# Power.net
KiCad netlist of a schematic drawn in Altium Designer
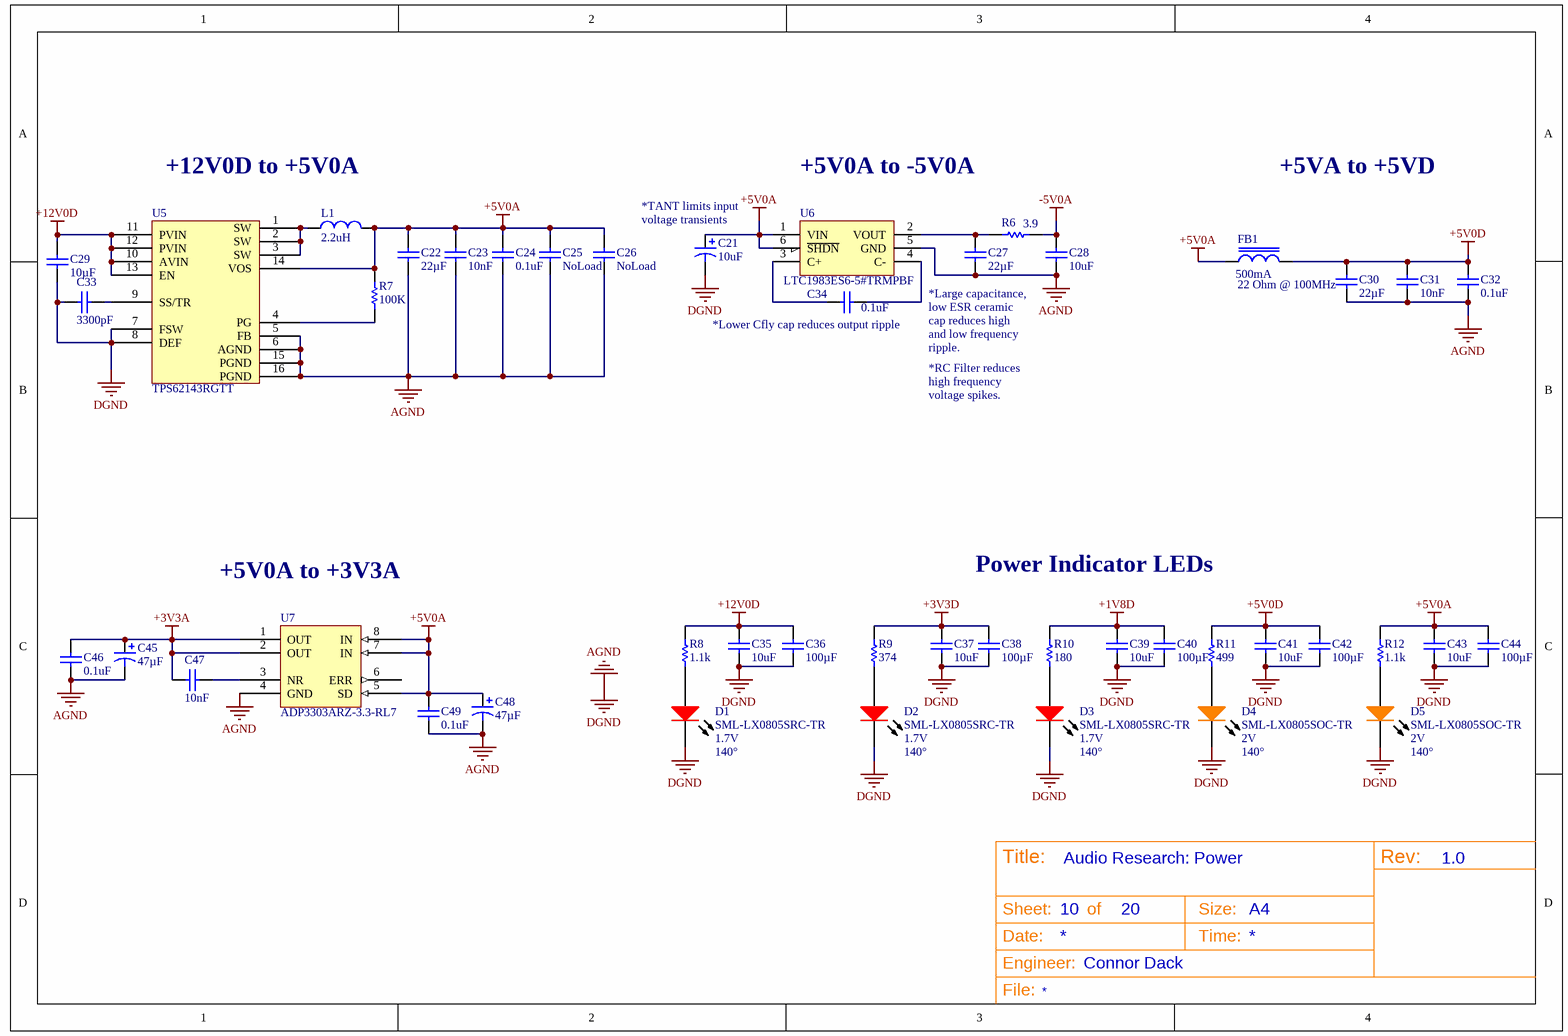
[diagram p0: Power.SchDoc]

(export (version "E")
  (design (tool "Eeschema 10.0.6"))
  (components
    (comp (ref "C21")
      (value "TR3A106K010C0900")
      (footprint "C1206_TANT")
      (description "CAP TANT 10UF 10V 10% 1206")
      (fields
        (field (name "MANUFACTURER") "Vishay Sprague")
        (field (name "TOLERANCE") "10%")
        (field (name "CAPACITANCE") "10uF")
      )
      (libsource (lib "Schematic_Components_CD") (part "TR3A106K010C0900"))
    )
    (comp (ref "C22")
      (value "CL21A226KPCLRNC")
      (footprint "6-0805_L")
      (description "CAP CER 22UF 10V X5R 0805")
      (fields
        (field (name "MANUFACTURER") "Samsung Electro-Mechanics America, Inc.")
        (field (name "TOLERANCE") "±10%")
        (field (name "CAPACITANCE") "22µF")
      )
      (libsource (lib "Schematic_Components") (part "CL21A226KPCLRNC"))
    )
    (comp (ref "C23")
      (value "C1608X8R2A103K080AA")
      (footprint "3-0603_L")
      (description "CAP CER 10000PF 100V X8R 0603")
      (fields
        (field (name "MANUFACTURER") "TDK")
        (field (name "TOLERANCE") "10%")
        (field (name "CAPACITANCE") "10nF")
      )
      (libsource (lib "Schematic_Components_CD") (part "C1608X8R2A103K080AA"))
    )
    (comp (ref "C24")
      (value "CL10F104ZO8NNNC")
      (footprint "3-0603_L")
      (description "CAP CER 0.1UF 16V Y5V 0603")
      (fields
        (field (name "MANUFACTURER") "Samsung")
        (field (name "TOLERANCE") "80%")
        (field (name "CAPACITANCE") "0.1uF")
      )
      (libsource (lib "Schematic_Components_CD") (part "CL10F104ZO8NNNC"))
    )
    (comp (ref "C25")
      (value "CAP 0603")
      (footprint "3-0603_L")
      (description "CAP 0603 SMD - NoLoad")
      (fields (field (name "CAPACITANCE") "NoLoad"))
      (libsource (lib "Schematic_Components_CD") (part "CAP 0603"))
    )
    (comp (ref "C26")
      (value "CAP 0603")
      (footprint "3-0603_L")
      (description "CAP 0603 SMD - NoLoad")
      (fields (field (name "CAPACITANCE") "NoLoad"))
      (libsource (lib "Schematic_Components_CD") (part "CAP 0603"))
    )
    (comp (ref "C27")
      (value "C3216X6S1C226M")
      (footprint "C1206")
      (description "CAP CER 22UF 16V 20% X6S 1206")
      (fields
        (field (name "MANUFACTURER") "TDK Corporation")
        (field (name "TOLERANCE") "±20%")
        (field (name "CAPACITANCE") "22µF")
      )
      (libsource (lib "Schematic_Components") (part "C3216X6S1C226M"))
    )
    (comp (ref "C28")
      (value "GRM188R61A106ME69D")
      (footprint "3-0603_L")
      (description "CAP CER 10UF 10V X5R 0603")
      (fields
        (field (name "MANUFACTURER") "Murata")
        (field (name "TOLERANCE") "20%")
        (field (name "CAPACITANCE") "10uF")
      )
      (libsource (lib "Schematic_Components_CD") (part "GRM188R61A106ME69D"))
    )
    (comp (ref "C29")
      (value "C3216X5R1H106K")
      (footprint "C1206")
      (description "CAP CER 10UF 50V 10% X5R 1206")
      (fields
        (field (name "MANUFACTURER") "TDK Corporation")
        (field (name "TOLERANCE") "±10%")
        (field (name "CAPACITANCE") "10µF")
      )
      (libsource (lib "Schematic_Components") (part "C3216X5R1H106K"))
    )
    (comp (ref "C30")
      (value "CL21A226KPCLRNC")
      (footprint "6-0805_L")
      (description "CAP CER 22UF 10V X5R 0805")
      (fields
        (field (name "MANUFACTURER") "Samsung Electro-Mechanics America, Inc.")
        (field (name "TOLERANCE") "±10%")
        (field (name "CAPACITANCE") "22µF")
      )
      (libsource (lib "Schematic_Components") (part "CL21A226KPCLRNC"))
    )
    (comp (ref "C31")
      (value "C1608X8R2A103K080AA")
      (footprint "3-0603_L")
      (description "CAP CER 10000PF 100V X8R 0603")
      (fields
        (field (name "MANUFACTURER") "TDK")
        (field (name "TOLERANCE") "10%")
        (field (name "CAPACITANCE") "10nF")
      )
      (libsource (lib "Schematic_Components_CD") (part "C1608X8R2A103K080AA"))
    )
    (comp (ref "C32")
      (value "CL10F104ZO8NNNC")
      (footprint "3-0603_L")
      (description "CAP CER 0.1UF 16V Y5V 0603")
      (fields
        (field (name "MANUFACTURER") "Samsung")
        (field (name "TOLERANCE") "80%")
        (field (name "CAPACITANCE") "0.1uF")
      )
      (libsource (lib "Schematic_Components_CD") (part "CL10F104ZO8NNNC"))
    )
    (comp (ref "C33")
      (value "GRM2165C1H332JA01D")
      (footprint "6-0805_L")
      (description "CAP CER 3300PF 50V NP0 0805")
      (fields
        (field (name "MANUFACTURER") "Murata Electronics North America")
        (field (name "TOLERANCE") "±5%")
        (field (name "CAPACITANCE") "3300pF")
      )
      (libsource (lib "Schematic_Components") (part "GRM2165C1H332JA01D"))
    )
    (comp (ref "C34")
      (value "CL10F104ZO8NNNC")
      (footprint "3-0603_L")
      (description "CAP CER 0.1UF 16V Y5V 0603")
      (fields
        (field (name "MANUFACTURER") "Samsung")
        (field (name "TOLERANCE") "80%")
        (field (name "CAPACITANCE") "0.1uF")
      )
      (libsource (lib "Schematic_Components_CD") (part "CL10F104ZO8NNNC"))
    )
    (comp (ref "C35")
      (value "GRM188R61A106ME69D")
      (footprint "3-0603_L")
      (description "CAP CER 10UF 10V X5R 0603")
      (fields
        (field (name "MANUFACTURER") "Murata")
        (field (name "TOLERANCE") "20%")
        (field (name "CAPACITANCE") "10uF")
      )
      (libsource (lib "Schematic_Components_CD") (part "GRM188R61A106ME69D"))
    )
    (comp (ref "C36")
      (value "CL32X107MQVNNNE")
      (footprint "C1210X25_L")
      (description "100µF 6.3V Ceramic Capacitor X6S 1210 (3225 Metric) 0.126\" L x 0.098\" W (3.20mm x 2.50mm)")
      (fields
        (field (name "MANUFACTURER") "Samsung Electro-Mechanics America, Inc.")
        (field (name "TOLERANCE") "±20%")
        (field (name "CAPACITANCE") "100µF")
      )
      (libsource (lib "Schematic_Components") (part "CL32X107MQVNNNE"))
    )
    (comp (ref "C37")
      (value "GRM188R61A106ME69D")
      (footprint "3-0603_L")
      (description "CAP CER 10UF 10V X5R 0603")
      (fields
        (field (name "MANUFACTURER") "Murata")
        (field (name "TOLERANCE") "20%")
        (field (name "CAPACITANCE") "10uF")
      )
      (libsource (lib "Schematic_Components_CD") (part "GRM188R61A106ME69D"))
    )
    (comp (ref "C38")
      (value "CL32X107MQVNNNE")
      (footprint "C1210X25_L")
      (description "100µF 6.3V Ceramic Capacitor X6S 1210 (3225 Metric) 0.126\" L x 0.098\" W (3.20mm x 2.50mm)")
      (fields
        (field (name "MANUFACTURER") "Samsung Electro-Mechanics America, Inc.")
        (field (name "TOLERANCE") "±20%")
        (field (name "CAPACITANCE") "100µF")
      )
      (libsource (lib "Schematic_Components") (part "CL32X107MQVNNNE"))
    )
    (comp (ref "C39")
      (value "GRM188R61A106ME69D")
      (footprint "3-0603_L")
      (description "CAP CER 10UF 10V X5R 0603")
      (fields
        (field (name "MANUFACTURER") "Murata")
        (field (name "TOLERANCE") "20%")
        (field (name "CAPACITANCE") "10uF")
      )
      (libsource (lib "Schematic_Components_CD") (part "GRM188R61A106ME69D"))
    )
    (comp (ref "C40")
      (value "CL32X107MQVNNNE")
      (footprint "C1210X25_L")
      (description "100µF 6.3V Ceramic Capacitor X6S 1210 (3225 Metric) 0.126\" L x 0.098\" W (3.20mm x 2.50mm)")
      (fields
        (field (name "MANUFACTURER") "Samsung Electro-Mechanics America, Inc.")
        (field (name "TOLERANCE") "±20%")
        (field (name "CAPACITANCE") "100µF")
      )
      (libsource (lib "Schematic_Components") (part "CL32X107MQVNNNE"))
    )
    (comp (ref "C41")
      (value "GRM188R61A106ME69D")
      (footprint "3-0603_L")
      (description "CAP CER 10UF 10V X5R 0603")
      (fields
        (field (name "MANUFACTURER") "Murata")
        (field (name "TOLERANCE") "20%")
        (field (name "CAPACITANCE") "10uF")
      )
      (libsource (lib "Schematic_Components_CD") (part "GRM188R61A106ME69D"))
    )
    (comp (ref "C42")
      (value "CL32X107MQVNNNE")
      (footprint "C1210X25_L")
      (description "100µF 6.3V Ceramic Capacitor X6S 1210 (3225 Metric) 0.126\" L x 0.098\" W (3.20mm x 2.50mm)")
      (fields
        (field (name "MANUFACTURER") "Samsung Electro-Mechanics America, Inc.")
        (field (name "TOLERANCE") "±20%")
        (field (name "CAPACITANCE") "100µF")
      )
      (libsource (lib "Schematic_Components") (part "CL32X107MQVNNNE"))
    )
    (comp (ref "C43")
      (value "GRM188R61A106ME69D")
      (footprint "3-0603_L")
      (description "CAP CER 10UF 10V X5R 0603")
      (fields
        (field (name "MANUFACTURER") "Murata")
        (field (name "TOLERANCE") "20%")
        (field (name "CAPACITANCE") "10uF")
      )
      (libsource (lib "Schematic_Components_CD") (part "GRM188R61A106ME69D"))
    )
    (comp (ref "C44")
      (value "CL32X107MQVNNNE")
      (footprint "C1210X25_L")
      (description "100µF 6.3V Ceramic Capacitor X6S 1210 (3225 Metric) 0.126\" L x 0.098\" W (3.20mm x 2.50mm)")
      (fields
        (field (name "MANUFACTURER") "Samsung Electro-Mechanics America, Inc.")
        (field (name "TOLERANCE") "±20%")
        (field (name "CAPACITANCE") "100µF")
      )
      (libsource (lib "Schematic_Components") (part "CL32X107MQVNNNE"))
    )
    (comp (ref "C45")
      (value "EEE-FT1H470AP")
      (footprint "ALUMCAPC630D_D")
      (description "CAP ALUM 47UF 50V 20% SMD")
      (fields
        (field (name "MANUFACTURER") "Panasonic - ECG")
        (field (name "TOLERANCE") "±20%")
        (field (name "CAPACITANCE") "47µF")
      )
      (libsource (lib "Schematic_Components") (part "EEE-FT1H470AP"))
    )
    (comp (ref "C46")
      (value "CL10F104ZO8NNNC")
      (footprint "3-0603_L")
      (description "CAP CER 0.1UF 16V Y5V 0603")
      (fields
        (field (name "MANUFACTURER") "Samsung")
        (field (name "TOLERANCE") "80%")
        (field (name "CAPACITANCE") "0.1uF")
      )
      (libsource (lib "Schematic_Components_CD") (part "CL10F104ZO8NNNC"))
    )
    (comp (ref "C47")
      (value "C1608X8R2A103K080AA")
      (footprint "3-0603_L")
      (description "CAP CER 10000PF 100V X8R 0603")
      (fields
        (field (name "MANUFACTURER") "TDK")
        (field (name "TOLERANCE") "10%")
        (field (name "CAPACITANCE") "10nF")
      )
      (libsource (lib "Schematic_Components_CD") (part "C1608X8R2A103K080AA"))
    )
    (comp (ref "C48")
      (value "EEE-FT1H470AP")
      (footprint "ALUMCAPC630D_D")
      (description "CAP ALUM 47UF 50V 20% SMD")
      (fields
        (field (name "MANUFACTURER") "Panasonic - ECG")
        (field (name "TOLERANCE") "±20%")
        (field (name "CAPACITANCE") "47µF")
      )
      (libsource (lib "Schematic_Components") (part "EEE-FT1H470AP"))
    )
    (comp (ref "C49")
      (value "CL10F104ZO8NNNC")
      (footprint "3-0603_L")
      (description "CAP CER 0.1UF 16V Y5V 0603")
      (fields
        (field (name "MANUFACTURER") "Samsung")
        (field (name "TOLERANCE") "80%")
        (field (name "CAPACITANCE") "0.1uF")
      )
      (libsource (lib "Schematic_Components_CD") (part "CL10F104ZO8NNNC"))
    )
    (comp (ref "D1")
      (value "LED_RED 4")
      (footprint "DIOM2012X12L_RED")
      (description "LED 660NM SUPER RED CLR 0805 T/R")
      (fields
        (field (name "MANUFACTURER") "Lumex Opto/Components Inc")
        (field (name "MANUFACTURER PART NUMBER") "SML-LX0805SRC-TR")
        (field (name "VOLTAGE - FORWARD (VF) (TYP)") "1.7V")
        (field (name "VIEWING ANGLE") "140°")
      )
      (libsource (lib "Schematic_Components") (part "LED_RED 4"))
    )
    (comp (ref "D2")
      (value "LED_RED 4")
      (footprint "DIOM2012X12L_RED")
      (description "LED 660NM SUPER RED CLR 0805 T/R")
      (fields
        (field (name "MANUFACTURER") "Lumex Opto/Components Inc")
        (field (name "MANUFACTURER PART NUMBER") "SML-LX0805SRC-TR")
        (field (name "VOLTAGE - FORWARD (VF) (TYP)") "1.7V")
        (field (name "VIEWING ANGLE") "140°")
      )
      (libsource (lib "Schematic_Components") (part "LED_RED 4"))
    )
    (comp (ref "D3")
      (value "LED_RED 4")
      (footprint "DIOM2012X12L_RED")
      (description "LED 660NM SUPER RED CLR 0805 T/R")
      (fields
        (field (name "MANUFACTURER") "Lumex Opto/Components Inc")
        (field (name "MANUFACTURER PART NUMBER") "SML-LX0805SRC-TR")
        (field (name "VOLTAGE - FORWARD (VF) (TYP)") "1.7V")
        (field (name "VIEWING ANGLE") "140°")
      )
      (libsource (lib "Schematic_Components") (part "LED_RED 4"))
    )
    (comp (ref "D4")
      (value "LED_ORANGE 3")
      (footprint "DIOM2012X12L_ORANGE")
      (description "LED 610NM SUPER ORANGE 0805 SMD")
      (fields
        (field (name "MANUFACTURER") "Lumex Opto/Components Inc")
        (field (name "MANUFACTURER PART NUMBER") "SML-LX0805SOC-TR")
        (field (name "VOLTAGE - FORWARD (VF) (TYP)") "2V")
        (field (name "VIEWING ANGLE") "140°")
      )
      (libsource (lib "Schematic_Components") (part "LED_ORANGE 3"))
    )
    (comp (ref "D5")
      (value "LED_ORANGE 3")
      (footprint "DIOM2012X12L_ORANGE")
      (description "LED 610NM SUPER ORANGE 0805 SMD")
      (fields
        (field (name "MANUFACTURER") "Lumex Opto/Components Inc")
        (field (name "MANUFACTURER PART NUMBER") "SML-LX0805SOC-TR")
        (field (name "VOLTAGE - FORWARD (VF) (TYP)") "2V")
        (field (name "VIEWING ANGLE") "140°")
      )
      (libsource (lib "Schematic_Components") (part "LED_ORANGE 3"))
    )
    (comp (ref "FB1")
      (value "BLM18BA220SN1D")
      (footprint "3-0603_L")
      (description "FERRITE CHIP 22 OHM 500MA 0603")
      (fields
        (field (name "MANUFACTURER") "Murata Electronics North America")
        (field (name "CURRENT RATING") "500mA")
        (field (name "IMPEDANCE @ FREQUENCY") "22 Ohm @ 100MHz")
      )
      (libsource (lib "Schematic_Components") (part "BLM18BA220SN1D"))
    )
    (comp (ref "L1")
      (value "2.2uH Ind")
      (footprint "XFL4020")
      (description "Fixed Inductors XFL4020 AEC-Q200 2.2 uH 20 % 8 A")
      (fields
        (field (name "MANUFACTURER") "Coilcraft")
        (field (name "TOLERANCE") "20%")
        (field (name "INDUCTANCE") "2.2uH")
      )
      (libsource (lib "Schematic_Components_CD") (part "XFL4020-222MEB"))
    )
    (comp (ref "R6")
      (value "ERJ-3RQF3R9V")
      (footprint "3-0603_R_L")
      (description "RES 3.9 OHM 1/10W 1% 0603 SMD")
      (fields
        (field (name "MANUFACTURER") "Panasonic Electronic Components")
        (field (name "TOLERANCE") "±1%")
        (field (name "RESISTANCE (OHMS)") "3.9")
      )
      (libsource (lib "Schematic_Components") (part "ERJ-3RQF3R9V"))
    )
    (comp (ref "R7")
      (value "ERJ-3EKF1003V")
      (footprint "3-0603_R_L")
      (description "RES 100K OHM 1/10W 1% 0603 SMD")
      (fields
        (field (name "MANUFACTURER") "Panasonic - ECG")
        (field (name "TOLERANCE") "±1%")
        (field (name "RESISTANCE (OHMS)") "100K")
      )
      (libsource (lib "Schematic_Components") (part "ERJ-3EKF1003V"))
    )
    (comp (ref "R8")
      (value "RMCF0603FT1K10")
      (footprint "3-0603_R_L")
      (description "RES 1.1K OHM 1% 1/10W 0603")
      (fields
        (field (name "MANUFACTURER") "Stackpole Electronics")
        (field (name "TOLERANCE") "1%")
        (field (name "RESISTANCE") "1.1k")
      )
      (libsource (lib "Schematic_Components_CD") (part "RMCF0603FT1K10"))
    )
    (comp (ref "R9")
      (value "ERJ-3EKF3740V")
      (footprint "3-0603_R_L")
      (description "RES SMD 374 OHM 1% 1/10W 0603")
      (fields
        (field (name "MANUFACTURER") "Panasonic Electronic Components")
        (field (name "TOLERANCE") "±1%")
        (field (name "RESISTANCE (OHMS)") "374")
      )
      (libsource (lib "Schematic_Components") (part "ERJ-3EKF3740V"))
    )
    (comp (ref "R10")
      (value "ERA-3AEB181V")
      (footprint "3-0603_R_L")
      (description "RES SMD 180 OHM 0.1% 1/10W 0603")
      (fields
        (field (name "MANUFACTURER") "Panasonic")
        (field (name "MANUFACTURER PART NUMBER") "ERA3AEB181V")
        (field (name "RESISTANCE") "180")
      )
      (libsource (lib "Schematic_Components_CD") (part "ERA-3AEB181V"))
    )
    (comp (ref "R11")
      (value "ERJ-3EKF4990V")
      (footprint "3-0603_R_L")
      (description "RES 499 OHM 1/10W 1% 0603 SMD")
      (fields
        (field (name "MANUFACTURER") "Panasonic - ECG")
        (field (name "TOLERANCE") "±1%")
        (field (name "RESISTANCE (OHMS)") "499")
      )
      (libsource (lib "Schematic_Components") (part "ERJ-3EKF4990V"))
    )
    (comp (ref "R12")
      (value "RMCF0603FT1K10")
      (footprint "3-0603_R_L")
      (description "RES 1.1K OHM 1% 1/10W 0603")
      (fields
        (field (name "MANUFACTURER") "Stackpole Electronics")
        (field (name "TOLERANCE") "1%")
        (field (name "RESISTANCE") "1.1k")
      )
      (libsource (lib "Schematic_Components_CD") (part "RMCF0603FT1K10"))
    )
    (comp (ref "U5")
      (value "IC REG BUCK 5V 2A SYNC 16QFN")
      (footprint "QFN50P300X300X100_HS-17N")
      (description "Buck Switching Regulator IC Positive Fixed 5V 1 Output 2A 16-VFQFN Exposed Pad")
      (fields
        (field (name "MANUFACTURER") "Texas Instruments")
        (field (name "MANUFACTURER PART NUMBER") "TPS62143RGTT")
      )
      (libsource (lib "Schematic_Components_CD") (part "TPS62143RGTT"))
    )
    (comp (ref "U6")
      (value "~")
      (footprint "SOT23-6_L")
      (description "IC REG SWITCHD CAP INV -5V SOT23")
      (fields
        (field (name "MANUFACTURER") "Linear Technology")
        (field (name "MANUFACTURER PART NUMBER") "LTC1983ES6-5#TRMPBF")
      )
      (libsource (lib "Schematic_Components") (part "LTC1983ES6-5#TRMPBF"))
    )
    (comp (ref "U7")
      (value "ADP3303ARZ-3.3-RL7")
      (footprint "SOIC127P600X175-8L")
      (description "Linear Voltage Regulator IC Positive Fixed 1 Output 3.3V 200mA 8-SOIC")
      (fields
        (field (name "MANUFACTURER") "Analog Devices Inc.")
        (field (name "MANUFACTURER PART NUMBER") "ADP3303ARZ-3.3-RL7")
      )
      (libsource (lib "NIH_DE0_Nano_Daughter_Card_Library") (part "ADP3303ARZ-3.3-RL7"))
    )
  )
  (nets
    (net (code "1") (name "+1V8D") (class "Default")
      (node (ref "C39") (pin "2") (pinfunction "2_2") (pintype "passive"))
      (node (ref "C40") (pin "2") (pinfunction "2_2") (pintype "passive"))
      (node (ref "R10") (pin "2") (pinfunction "2_2") (pintype "passive"))
    )
    (net (code "2") (name "+3V3A") (class "Default")
      (node (ref "C45") (pin "1") (pinfunction "P_1") (pintype "passive"))
      (node (ref "C46") (pin "1") (pinfunction "1_1") (pintype "passive"))
      (node (ref "C47") (pin "1") (pinfunction "1_1") (pintype "passive"))
      (node (ref "U7") (pin "1") (pinfunction "OUT_1") (pintype "passive"))
      (node (ref "U7") (pin "2") (pinfunction "OUT_2") (pintype "passive"))
    )
    (net (code "3") (name "+3V3D") (class "Default")
      (node (ref "C37") (pin "2") (pinfunction "2_2") (pintype "passive"))
      (node (ref "C38") (pin "2") (pinfunction "2_2") (pintype "passive"))
      (node (ref "R9") (pin "2") (pinfunction "2_2") (pintype "passive"))
    )
    (net (code "4") (name "+5V0A") (class "Default")
      (node (ref "C21") (pin "1") (pinfunction "P_1") (pintype "passive"))
      (node (ref "C22") (pin "2") (pinfunction "2_2") (pintype "passive"))
      (node (ref "C23") (pin "2") (pinfunction "2_2") (pintype "passive"))
      (node (ref "C24") (pin "1") (pinfunction "1_1") (pintype "passive"))
      (node (ref "C25") (pin "2") (pinfunction "2_2") (pintype "passive"))
      (node (ref "C26") (pin "2") (pinfunction "2_2") (pintype "passive"))
      (node (ref "C43") (pin "2") (pinfunction "2_2") (pintype "passive"))
      (node (ref "C44") (pin "2") (pinfunction "2_2") (pintype "passive"))
      (node (ref "C48") (pin "1") (pinfunction "P_1") (pintype "passive"))
      (node (ref "C49") (pin "1") (pinfunction "1_1") (pintype "passive"))
      (node (ref "FB1") (pin "1") (pinfunction "1_1") (pintype "passive"))
      (node (ref "L1") (pin "2") (pinfunction "2_2") (pintype "passive"))
      (node (ref "R12") (pin "2") (pinfunction "2_2") (pintype "passive"))
      (node (ref "R7") (pin "2") (pinfunction "2_2") (pintype "passive"))
      (node (ref "U5") (pin "14") (pinfunction "VOS_14") (pintype "passive"))
      (node (ref "U6") (pin "1") (pinfunction "VIN_1") (pintype "power_in"))
      (node (ref "U6") (pin "6") (pinfunction "SHDN_6") (pintype "passive"))
      (node (ref "U7") (pin "5") (pinfunction "SD_5") (pintype "input"))
      (node (ref "U7") (pin "7") (pinfunction "IN_7") (pintype "input"))
      (node (ref "U7") (pin "8") (pinfunction "IN_8") (pintype "input"))
    )
    (net (code "5") (name "+5V0D") (class "Default")
      (node (ref "C30") (pin "2") (pinfunction "2_2") (pintype "passive"))
      (node (ref "C31") (pin "2") (pinfunction "2_2") (pintype "passive"))
      (node (ref "C32") (pin "1") (pinfunction "1_1") (pintype "passive"))
      (node (ref "C41") (pin "2") (pinfunction "2_2") (pintype "passive"))
      (node (ref "C42") (pin "2") (pinfunction "2_2") (pintype "passive"))
      (node (ref "FB1") (pin "2") (pinfunction "2_2") (pintype "passive"))
      (node (ref "R11") (pin "2") (pinfunction "2_2") (pintype "passive"))
    )
    (net (code "6") (name "+12V0D") (class "Default")
      (node (ref "C29") (pin "2") (pinfunction "2_2") (pintype "passive"))
      (node (ref "C35") (pin "2") (pinfunction "2_2") (pintype "passive"))
      (node (ref "C36") (pin "2") (pinfunction "2_2") (pintype "passive"))
      (node (ref "R8") (pin "2") (pinfunction "2_2") (pintype "passive"))
      (node (ref "U5") (pin "10") (pinfunction "AVIN_10") (pintype "passive"))
      (node (ref "U5") (pin "11") (pinfunction "PVIN_11") (pintype "passive"))
      (node (ref "U5") (pin "12") (pinfunction "PVIN_12") (pintype "passive"))
      (node (ref "U5") (pin "13") (pinfunction "EN_13") (pintype "passive"))
    )
    (net (code "7") (name "-5V0A") (class "Default")
      (node (ref "C28") (pin "2") (pinfunction "2_2") (pintype "passive"))
      (node (ref "R6") (pin "2") (pinfunction "2_2") (pintype "passive"))
    )
    (net (code "8") (name "AGND") (class "Default")
      (node (ref "C21") (pin "2") (pinfunction "N_2") (pintype "passive"))
      (node (ref "C22") (pin "1") (pinfunction "1_1") (pintype "passive"))
      (node (ref "C23") (pin "1") (pinfunction "1_1") (pintype "passive"))
      (node (ref "C24") (pin "2") (pinfunction "2_2") (pintype "passive"))
      (node (ref "C25") (pin "1") (pinfunction "1_1") (pintype "passive"))
      (node (ref "C26") (pin "1") (pinfunction "1_1") (pintype "passive"))
      (node (ref "C27") (pin "1") (pinfunction "1_1") (pintype "passive"))
      (node (ref "C28") (pin "1") (pinfunction "1_1") (pintype "passive"))
      (node (ref "C29") (pin "1") (pinfunction "1_1") (pintype "passive"))
      (node (ref "C30") (pin "1") (pinfunction "1_1") (pintype "passive"))
      (node (ref "C31") (pin "1") (pinfunction "1_1") (pintype "passive"))
      (node (ref "C32") (pin "2") (pinfunction "2_2") (pintype "passive"))
      (node (ref "C33") (pin "1") (pinfunction "1_1") (pintype "passive"))
      (node (ref "C35") (pin "1") (pinfunction "1_1") (pintype "passive"))
      (node (ref "C36") (pin "1") (pinfunction "1_1") (pintype "passive"))
      (node (ref "C37") (pin "1") (pinfunction "1_1") (pintype "passive"))
      (node (ref "C38") (pin "1") (pinfunction "1_1") (pintype "passive"))
      (node (ref "C39") (pin "1") (pinfunction "1_1") (pintype "passive"))
      (node (ref "C40") (pin "1") (pinfunction "1_1") (pintype "passive"))
      (node (ref "C41") (pin "1") (pinfunction "1_1") (pintype "passive"))
      (node (ref "C42") (pin "1") (pinfunction "1_1") (pintype "passive"))
      (node (ref "C43") (pin "1") (pinfunction "1_1") (pintype "passive"))
      (node (ref "C44") (pin "1") (pinfunction "1_1") (pintype "passive"))
      (node (ref "C45") (pin "2") (pinfunction "N_2") (pintype "passive"))
      (node (ref "C46") (pin "2") (pinfunction "2_2") (pintype "passive"))
      (node (ref "C48") (pin "2") (pinfunction "N_2") (pintype "passive"))
      (node (ref "C49") (pin "2") (pinfunction "2_2") (pintype "passive"))
      (node (ref "D1") (pin "2") (pinfunction "K_2") (pintype "passive"))
      (node (ref "D2") (pin "2") (pinfunction "K_2") (pintype "passive"))
      (node (ref "D3") (pin "2") (pinfunction "K_2") (pintype "passive"))
      (node (ref "D4") (pin "2") (pinfunction "K_2") (pintype "passive"))
      (node (ref "D5") (pin "2") (pinfunction "K_2") (pintype "passive"))
      (node (ref "U5") (pin "15") (pinfunction "PGND_15") (pintype "passive"))
      (node (ref "U5") (pin "16") (pinfunction "PGND_16") (pintype "passive"))
      (node (ref "U5") (pin "5") (pinfunction "FB_5") (pintype "passive"))
      (node (ref "U5") (pin "6") (pinfunction "AGND_6") (pintype "passive"))
      (node (ref "U5") (pin "7") (pinfunction "FSW_7") (pintype "passive"))
      (node (ref "U5") (pin "8") (pinfunction "DEF_8") (pintype "passive"))
      (node (ref "U6") (pin "5") (pinfunction "GND_5") (pintype "passive"))
      (node (ref "U7") (pin "4") (pinfunction "GND_4") (pintype "passive"))
    )
    (net (code "9") (name "Net-(D1-A)") (class "Default")
      (node (ref "D1") (pin "1") (pinfunction "A_1") (pintype "passive"))
      (node (ref "R8") (pin "1") (pinfunction "1_1") (pintype "passive"))
    )
    (net (code "10") (name "Net-(D2-A)") (class "Default")
      (node (ref "D2") (pin "1") (pinfunction "A_1") (pintype "passive"))
      (node (ref "R9") (pin "1") (pinfunction "1_1") (pintype "passive"))
    )
    (net (code "11") (name "Net-(D3-A)") (class "Default")
      (node (ref "D3") (pin "1") (pinfunction "A_1") (pintype "passive"))
      (node (ref "R10") (pin "1") (pinfunction "1_1") (pintype "passive"))
    )
    (net (code "12") (name "Net-(D4-A)") (class "Default")
      (node (ref "D4") (pin "1") (pinfunction "A_1") (pintype "passive"))
      (node (ref "R11") (pin "1") (pinfunction "1_1") (pintype "passive"))
    )
    (net (code "13") (name "Net-(D5-A)") (class "Default")
      (node (ref "D5") (pin "1") (pinfunction "A_1") (pintype "passive"))
      (node (ref "R12") (pin "1") (pinfunction "1_1") (pintype "passive"))
    )
    (net (code "14") (name "Net-(L1-Pad1)") (class "Default")
      (node (ref "L1") (pin "1") (pinfunction "1_1") (pintype "passive"))
      (node (ref "U5") (pin "1") (pinfunction "SW_1") (pintype "passive"))
      (node (ref "U5") (pin "2") (pinfunction "SW_2") (pintype "passive"))
      (node (ref "U5") (pin "3") (pinfunction "SW_3") (pintype "passive"))
    )
    (net (code "15") (name "Net-(U5-PG)") (class "Default")
      (node (ref "R7") (pin "1") (pinfunction "1_1") (pintype "passive"))
      (node (ref "U5") (pin "4") (pinfunction "PG_4") (pintype "passive"))
    )
    (net (code "16") (name "Net-(U5-SS{slash}TR)") (class "Default")
      (node (ref "C33") (pin "2") (pinfunction "2_2") (pintype "passive"))
      (node (ref "U5") (pin "9") (pinfunction "SS/TR_9") (pintype "passive"))
    )
    (net (code "17") (name "Net-(U6-C+)") (class "Default")
      (node (ref "C34") (pin "1") (pinfunction "1_1") (pintype "passive"))
      (node (ref "U6") (pin "3") (pinfunction "C+_3") (pintype "passive"))
    )
    (net (code "18") (name "Net-(U6-C-)") (class "Default")
      (node (ref "C34") (pin "2") (pinfunction "2_2") (pintype "passive"))
      (node (ref "U6") (pin "4") (pinfunction "C-_4") (pintype "passive"))
    )
    (net (code "19") (name "Net-(U6-VOUT)") (class "Default")
      (node (ref "C27") (pin "2") (pinfunction "2_2") (pintype "passive"))
      (node (ref "R6") (pin "1") (pinfunction "1_1") (pintype "passive"))
      (node (ref "U6") (pin "2") (pinfunction "VOUT_2") (pintype "power_in"))
    )
    (net (code "20") (name "Net-(U7-NR)") (class "Default")
      (node (ref "C47") (pin "2") (pinfunction "2_2") (pintype "passive"))
      (node (ref "U7") (pin "3") (pinfunction "NR_3") (pintype "passive"))
    )
    (net (code "21") (name "unconnected-(U7-ERR-Pad6)") (class "Default")
      (node (ref "U7") (pin "6") (pinfunction "ERR_6") (pintype "output"))
    )
  )
)
